# axiom_beta_shield_genio_v0_3_r1_2_ac7f6a.net
KiCad netlist of a schematic drawn in EAGLE
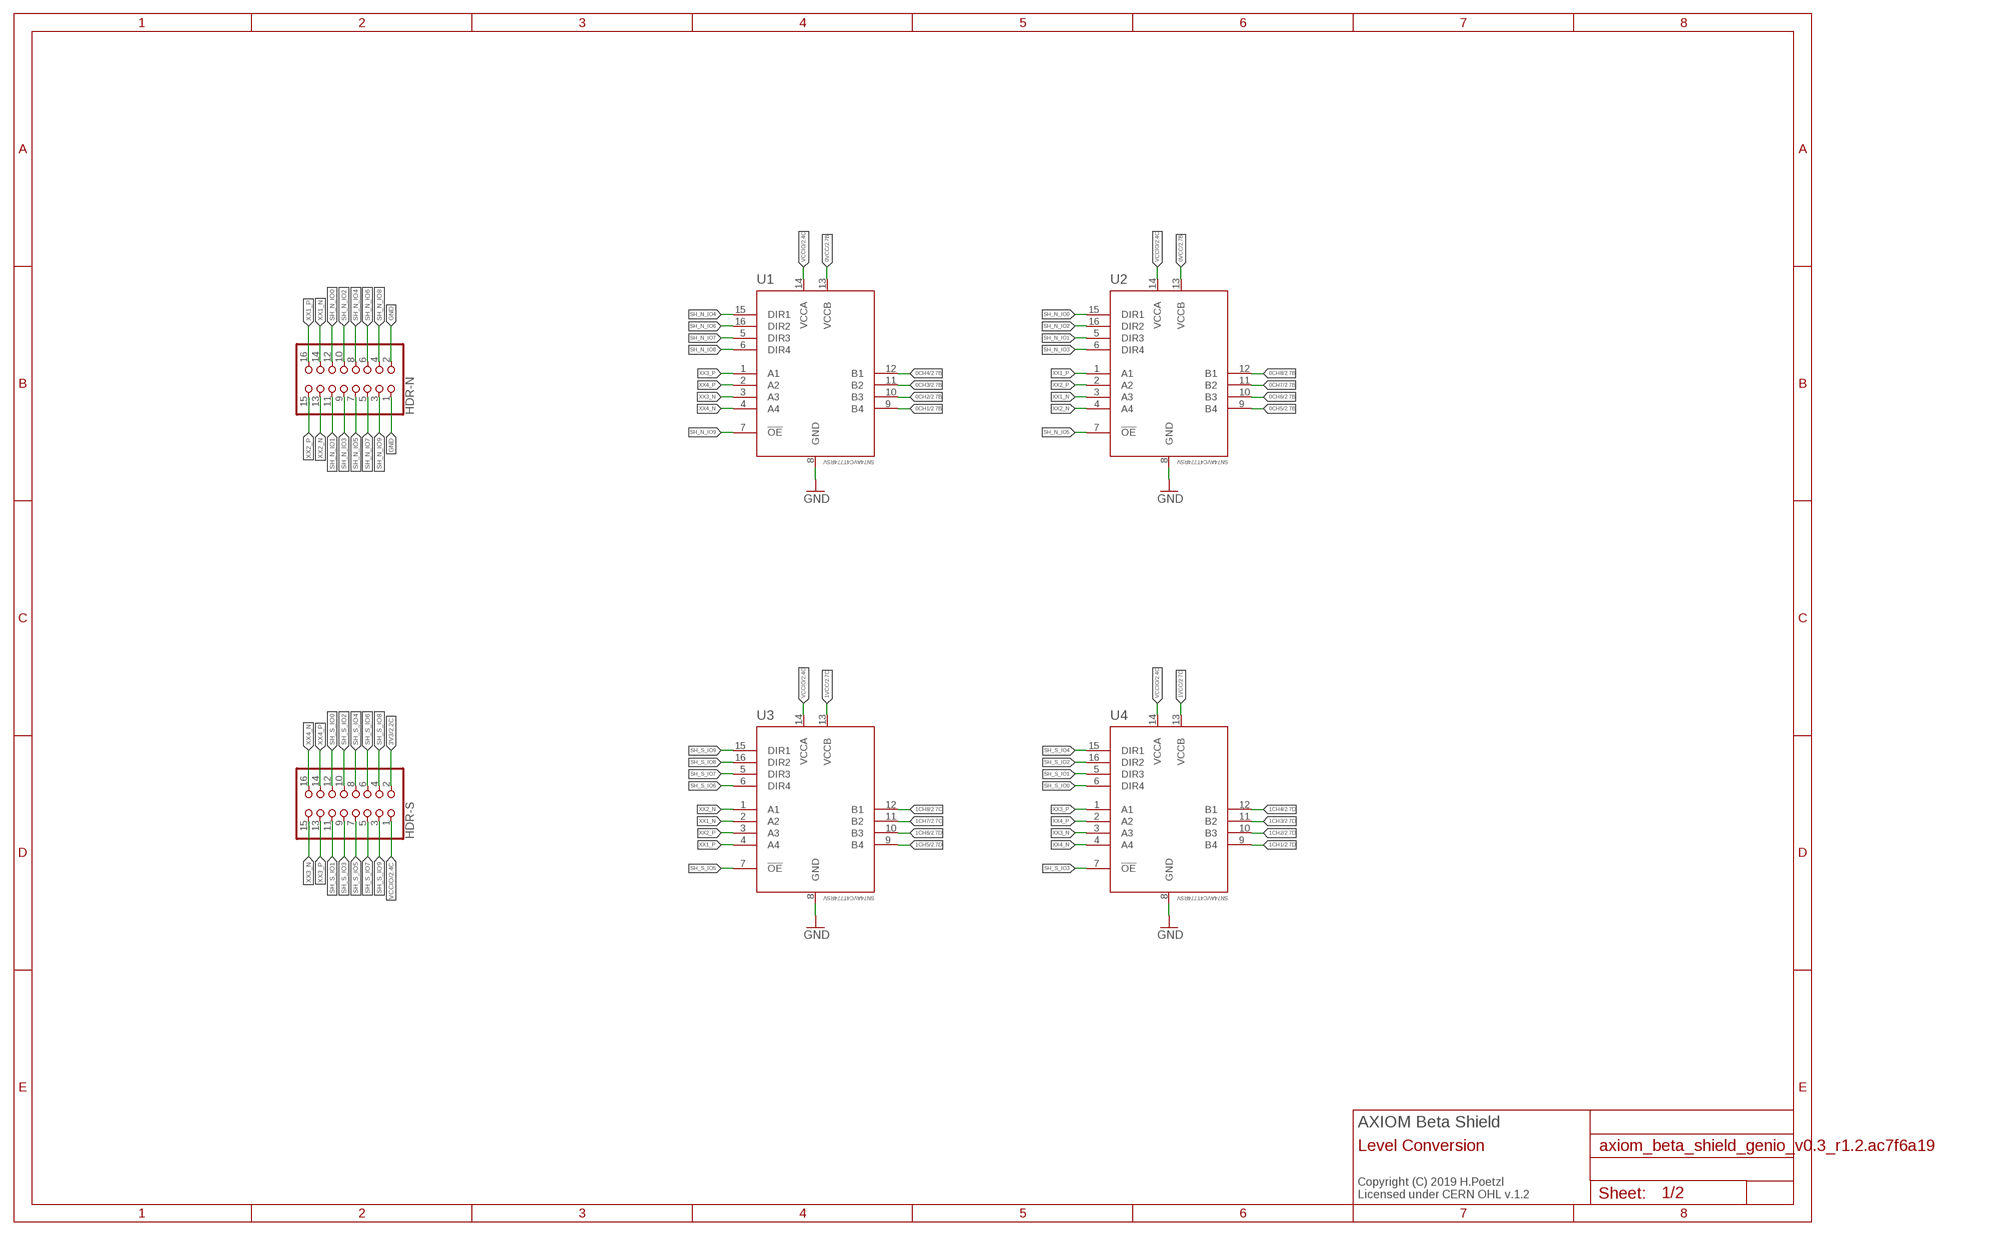
[diagram p0: schematic, sheet 1]
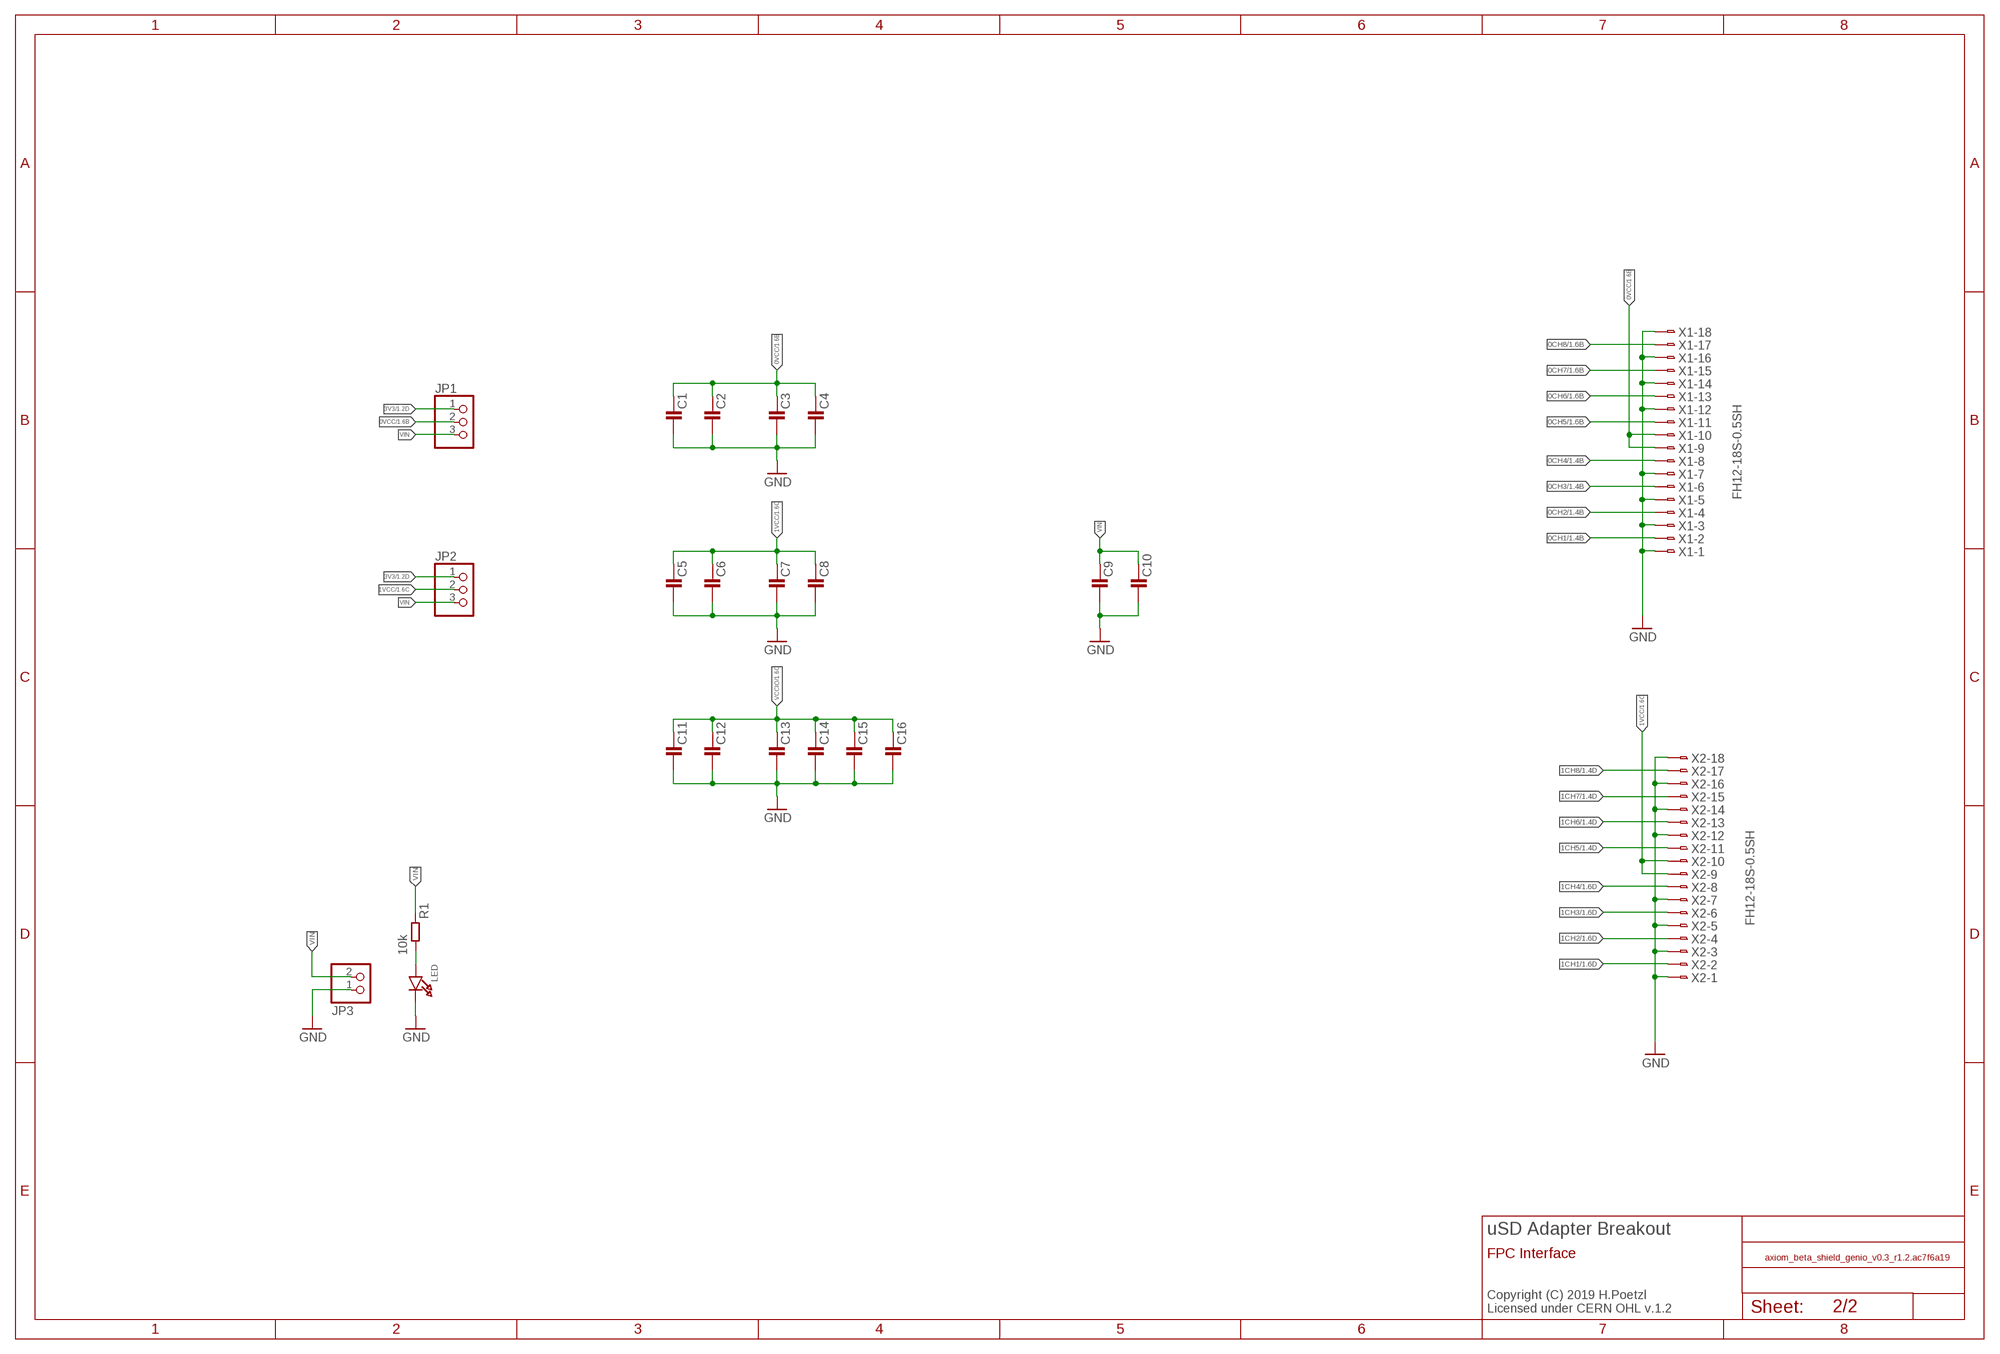
[diagram p1: schematic, sheet 2]

(export (version "E")
  (design (tool "Eeschema 10.0.6"))
  (components
    (comp (ref "HDR-N")
      (value "PINHD-2X08_2.00_SMD")
      (footprint "eagle-import:2X08M_SMD")
      (libsource (lib "eagle-import") (part "PINHD-2X08_2.00_SMD"))
    )
    (comp (ref "HDR-S")
      (value "PINHD-2X08_2.00_SMD")
      (footprint "eagle-import:2X08M_SMD")
      (libsource (lib "eagle-import") (part "PINHD-2X08_2.00_SMD"))
    )
    (comp (ref "U1")
      (value "SN74AVC4T774RSV")
      (footprint "eagle-import:QFN40P185X265X55-16N")
      (libsource (lib "eagle-import") (part "SN74AVC4T774RSV"))
    )
    (comp (ref "U2")
      (value "SN74AVC4T774RSV")
      (footprint "eagle-import:QFN40P185X265X55-16N")
      (libsource (lib "eagle-import") (part "SN74AVC4T774RSV"))
    )
    (comp (ref "U3")
      (value "SN74AVC4T774RSV")
      (footprint "eagle-import:QFN40P185X265X55-16N")
      (libsource (lib "eagle-import") (part "SN74AVC4T774RSV"))
    )
    (comp (ref "U4")
      (value "SN74AVC4T774RSV")
      (footprint "eagle-import:QFN40P185X265X55-16N")
      (libsource (lib "eagle-import") (part "SN74AVC4T774RSV"))
    )
    (comp (ref "C1")
      (value "C0603-C")
      (footprint "eagle-import:0603-C")
      (libsource (lib "eagle-import") (part "C0603-C"))
    )
    (comp (ref "C2")
      (value "C0603-C")
      (footprint "eagle-import:0603-C")
      (libsource (lib "eagle-import") (part "C0603-C"))
    )
    (comp (ref "C3")
      (value "C0402-C")
      (footprint "eagle-import:0402-C")
      (libsource (lib "eagle-import") (part "C0402-C"))
    )
    (comp (ref "C4")
      (value "C0402-C")
      (footprint "eagle-import:0402-C")
      (libsource (lib "eagle-import") (part "C0402-C"))
    )
    (comp (ref "C5")
      (value "C0603-C")
      (footprint "eagle-import:0603-C")
      (libsource (lib "eagle-import") (part "C0603-C"))
    )
    (comp (ref "C6")
      (value "C0603-C")
      (footprint "eagle-import:0603-C")
      (libsource (lib "eagle-import") (part "C0603-C"))
    )
    (comp (ref "C7")
      (value "C0402-C")
      (footprint "eagle-import:0402-C")
      (libsource (lib "eagle-import") (part "C0402-C"))
    )
    (comp (ref "C8")
      (value "C0402-C")
      (footprint "eagle-import:0402-C")
      (libsource (lib "eagle-import") (part "C0402-C"))
    )
    (comp (ref "C9")
      (value "C0603-C")
      (footprint "eagle-import:0603-C")
      (libsource (lib "eagle-import") (part "C0603-C"))
    )
    (comp (ref "C10")
      (value "C0603-C")
      (footprint "eagle-import:0603-C")
      (libsource (lib "eagle-import") (part "C0603-C"))
    )
    (comp (ref "C11")
      (value "C0603-C")
      (footprint "eagle-import:0603-C")
      (libsource (lib "eagle-import") (part "C0603-C"))
    )
    (comp (ref "C12")
      (value "C0603-C")
      (footprint "eagle-import:0603-C")
      (libsource (lib "eagle-import") (part "C0603-C"))
    )
    (comp (ref "C13")
      (value "C0402-C")
      (footprint "eagle-import:0402-C")
      (libsource (lib "eagle-import") (part "C0402-C"))
    )
    (comp (ref "C14")
      (value "C0402-C")
      (footprint "eagle-import:0402-C")
      (libsource (lib "eagle-import") (part "C0402-C"))
    )
    (comp (ref "C15")
      (value "C0402-C")
      (footprint "eagle-import:0402-C")
      (libsource (lib "eagle-import") (part "C0402-C"))
    )
    (comp (ref "C16")
      (value "C0402-C")
      (footprint "eagle-import:0402-C")
      (libsource (lib "eagle-import") (part "C0402-C"))
    )
    (comp (ref "JP1")
      (value "PINHD-1X03_2.00-90°-S")
      (footprint "eagle-import:1X03M_90-S")
      (libsource (lib "eagle-import") (part "PINHD-1X03_2.00-90°-S"))
    )
    (comp (ref "JP2")
      (value "PINHD-1X03_2.00-90°-S")
      (footprint "eagle-import:1X03M_90-S")
      (libsource (lib "eagle-import") (part "PINHD-1X03_2.00-90°-S"))
    )
    (comp (ref "JP3")
      (value "PINHD-1X02_2.54-90°")
      (footprint "eagle-import:1X02_90")
      (libsource (lib "eagle-import") (part "PINHD-1X02_2.54-90°"))
    )
    (comp (ref "LED")
      (value "LED0603_NOOUTLINE")
      (footprint "eagle-import:CHIPLED_0603_NOOUTLINE")
      (libsource (lib "eagle-import") (part "LED0603_NOOUTLINE"))
    )
    (comp (ref "R1")
      (value "10k")
      (footprint "eagle-import:0402-B")
      (libsource (lib "eagle-import") (part "R0402-B"))
    )
    (comp (ref "X1")
      (value "FH12-18S-0.5SH")
      (footprint "eagle-import:FH12-18S-0.5SH")
      (fields (field (name "MPN") "FH12-18S-0.5SH(55)"))
      (libsource (lib "eagle-import") (part "FH12-18S-0.5SH"))
    )
    (comp (ref "X2")
      (value "FH12-18S-0.5SH")
      (footprint "eagle-import:FH12-18S-0.5SH")
      (fields (field (name "MPN") "FH12-18S-0.5SH(55)"))
      (libsource (lib "eagle-import") (part "FH12-18S-0.5SH"))
    )
  )
  (nets
    (net (code "1") (name "0CH1") (class "Default")
      (node (ref "U1") (pin "9") (pinfunction "B4_9") (pintype "bidirectional"))
      (node (ref "X1") (pin "2") (pinfunction "1_2") (pintype "passive"))
    )
    (net (code "2") (name "0CH2") (class "Default")
      (node (ref "U1") (pin "10") (pinfunction "B3_10") (pintype "bidirectional"))
      (node (ref "X1") (pin "4") (pinfunction "1_4") (pintype "passive"))
    )
    (net (code "3") (name "0CH3") (class "Default")
      (node (ref "U1") (pin "11") (pinfunction "B2_11") (pintype "bidirectional"))
      (node (ref "X1") (pin "6") (pinfunction "1_6") (pintype "passive"))
    )
    (net (code "4") (name "0CH4") (class "Default")
      (node (ref "U1") (pin "12") (pinfunction "B1_12") (pintype "bidirectional"))
      (node (ref "X1") (pin "8") (pinfunction "1_8") (pintype "passive"))
    )
    (net (code "5") (name "0CH5") (class "Default")
      (node (ref "U2") (pin "9") (pinfunction "B4_9") (pintype "bidirectional"))
      (node (ref "X1") (pin "11") (pinfunction "1_11") (pintype "passive"))
    )
    (net (code "6") (name "0CH6") (class "Default")
      (node (ref "U2") (pin "10") (pinfunction "B3_10") (pintype "bidirectional"))
      (node (ref "X1") (pin "13") (pinfunction "1_13") (pintype "passive"))
    )
    (net (code "7") (name "0CH7") (class "Default")
      (node (ref "U2") (pin "11") (pinfunction "B2_11") (pintype "bidirectional"))
      (node (ref "X1") (pin "15") (pinfunction "1_15") (pintype "passive"))
    )
    (net (code "8") (name "0CH8") (class "Default")
      (node (ref "U2") (pin "12") (pinfunction "B1_12") (pintype "bidirectional"))
      (node (ref "X1") (pin "17") (pinfunction "1_17") (pintype "passive"))
    )
    (net (code "9") (name "0VCC") (class "Default")
      (node (ref "C1") (pin "1") (pinfunction "1_1") (pintype "passive"))
      (node (ref "C2") (pin "1") (pinfunction "1_1") (pintype "passive"))
      (node (ref "C3") (pin "1") (pinfunction "1_1") (pintype "passive"))
      (node (ref "C4") (pin "1") (pinfunction "1_1") (pintype "passive"))
      (node (ref "JP1") (pin "2") (pinfunction "2_2") (pintype "passive"))
      (node (ref "U1") (pin "13") (pinfunction "VCCB_13") (pintype "power_in"))
      (node (ref "U2") (pin "13") (pinfunction "VCCB_13") (pintype "power_in"))
      (node (ref "X1") (pin "10") (pinfunction "1_10") (pintype "passive"))
      (node (ref "X1") (pin "9") (pinfunction "1_9") (pintype "passive"))
    )
    (net (code "10") (name "1CH1") (class "Default")
      (node (ref "U4") (pin "9") (pinfunction "B4_9") (pintype "bidirectional"))
      (node (ref "X2") (pin "2") (pinfunction "1_2") (pintype "passive"))
    )
    (net (code "11") (name "1CH2") (class "Default")
      (node (ref "U4") (pin "10") (pinfunction "B3_10") (pintype "bidirectional"))
      (node (ref "X2") (pin "4") (pinfunction "1_4") (pintype "passive"))
    )
    (net (code "12") (name "1CH3") (class "Default")
      (node (ref "U4") (pin "11") (pinfunction "B2_11") (pintype "bidirectional"))
      (node (ref "X2") (pin "6") (pinfunction "1_6") (pintype "passive"))
    )
    (net (code "13") (name "1CH4") (class "Default")
      (node (ref "U4") (pin "12") (pinfunction "B1_12") (pintype "bidirectional"))
      (node (ref "X2") (pin "8") (pinfunction "1_8") (pintype "passive"))
    )
    (net (code "14") (name "1CH5") (class "Default")
      (node (ref "U3") (pin "9") (pinfunction "B4_9") (pintype "bidirectional"))
      (node (ref "X2") (pin "11") (pinfunction "1_11") (pintype "passive"))
    )
    (net (code "15") (name "1CH6") (class "Default")
      (node (ref "U3") (pin "10") (pinfunction "B3_10") (pintype "bidirectional"))
      (node (ref "X2") (pin "13") (pinfunction "1_13") (pintype "passive"))
    )
    (net (code "16") (name "1CH7") (class "Default")
      (node (ref "U3") (pin "11") (pinfunction "B2_11") (pintype "bidirectional"))
      (node (ref "X2") (pin "15") (pinfunction "1_15") (pintype "passive"))
    )
    (net (code "17") (name "1CH8") (class "Default")
      (node (ref "U3") (pin "12") (pinfunction "B1_12") (pintype "bidirectional"))
      (node (ref "X2") (pin "17") (pinfunction "1_17") (pintype "passive"))
    )
    (net (code "18") (name "1VCC") (class "Default")
      (node (ref "C5") (pin "1") (pinfunction "1_1") (pintype "passive"))
      (node (ref "C6") (pin "1") (pinfunction "1_1") (pintype "passive"))
      (node (ref "C7") (pin "1") (pinfunction "1_1") (pintype "passive"))
      (node (ref "C8") (pin "1") (pinfunction "1_1") (pintype "passive"))
      (node (ref "JP2") (pin "2") (pinfunction "2_2") (pintype "passive"))
      (node (ref "U3") (pin "13") (pinfunction "VCCB_13") (pintype "power_in"))
      (node (ref "U4") (pin "13") (pinfunction "VCCB_13") (pintype "power_in"))
      (node (ref "X2") (pin "10") (pinfunction "1_10") (pintype "passive"))
      (node (ref "X2") (pin "9") (pinfunction "1_9") (pintype "passive"))
    )
    (net (code "19") (name "3V3") (class "Default")
      (node (ref "HDR-S") (pin "2") (pinfunction "2_2") (pintype "passive"))
      (node (ref "JP1") (pin "1") (pinfunction "1_1") (pintype "passive"))
      (node (ref "JP2") (pin "1") (pinfunction "1_1") (pintype "passive"))
    )
    (net (code "20") (name "GND") (class "Default")
      (node (ref "C1") (pin "2") (pinfunction "2_2") (pintype "passive"))
      (node (ref "C10") (pin "2") (pinfunction "2_2") (pintype "passive"))
      (node (ref "C11") (pin "2") (pinfunction "2_2") (pintype "passive"))
      (node (ref "C12") (pin "2") (pinfunction "2_2") (pintype "passive"))
      (node (ref "C13") (pin "2") (pinfunction "2_2") (pintype "passive"))
      (node (ref "C14") (pin "2") (pinfunction "2_2") (pintype "passive"))
      (node (ref "C15") (pin "2") (pinfunction "2_2") (pintype "passive"))
      (node (ref "C16") (pin "2") (pinfunction "2_2") (pintype "passive"))
      (node (ref "C2") (pin "2") (pinfunction "2_2") (pintype "passive"))
      (node (ref "C3") (pin "2") (pinfunction "2_2") (pintype "passive"))
      (node (ref "C4") (pin "2") (pinfunction "2_2") (pintype "passive"))
      (node (ref "C5") (pin "2") (pinfunction "2_2") (pintype "passive"))
      (node (ref "C6") (pin "2") (pinfunction "2_2") (pintype "passive"))
      (node (ref "C7") (pin "2") (pinfunction "2_2") (pintype "passive"))
      (node (ref "C8") (pin "2") (pinfunction "2_2") (pintype "passive"))
      (node (ref "C9") (pin "2") (pinfunction "2_2") (pintype "passive"))
      (node (ref "HDR-N") (pin "1") (pinfunction "1_1") (pintype "passive"))
      (node (ref "HDR-N") (pin "2") (pinfunction "2_2") (pintype "passive"))
      (node (ref "JP3") (pin "1") (pinfunction "1_1") (pintype "passive"))
      (node (ref "LED") (pin "C") (pinfunction "C_C") (pintype "passive"))
      (node (ref "U1") (pin "8") (pinfunction "GND_8") (pintype "passive"))
      (node (ref "U2") (pin "8") (pinfunction "GND_8") (pintype "passive"))
      (node (ref "U3") (pin "8") (pinfunction "GND_8") (pintype "passive"))
      (node (ref "U4") (pin "8") (pinfunction "GND_8") (pintype "passive"))
      (node (ref "X1") (pin "1") (pinfunction "1_1") (pintype "passive"))
      (node (ref "X1") (pin "12") (pinfunction "1_12") (pintype "passive"))
      (node (ref "X1") (pin "14") (pinfunction "1_14") (pintype "passive"))
      (node (ref "X1") (pin "16") (pinfunction "1_16") (pintype "passive"))
      (node (ref "X1") (pin "18") (pinfunction "1_18") (pintype "passive"))
      (node (ref "X1") (pin "3") (pinfunction "1_3") (pintype "passive"))
      (node (ref "X1") (pin "5") (pinfunction "1_5") (pintype "passive"))
      (node (ref "X1") (pin "7") (pinfunction "1_7") (pintype "passive"))
      (node (ref "X2") (pin "1") (pinfunction "1_1") (pintype "passive"))
      (node (ref "X2") (pin "12") (pinfunction "1_12") (pintype "passive"))
      (node (ref "X2") (pin "14") (pinfunction "1_14") (pintype "passive"))
      (node (ref "X2") (pin "16") (pinfunction "1_16") (pintype "passive"))
      (node (ref "X2") (pin "18") (pinfunction "1_18") (pintype "passive"))
      (node (ref "X2") (pin "3") (pinfunction "1_3") (pintype "passive"))
      (node (ref "X2") (pin "5") (pinfunction "1_5") (pintype "passive"))
      (node (ref "X2") (pin "7") (pinfunction "1_7") (pintype "passive"))
    )
    (net (code "21") (name "Net-(LED-PadA)") (class "Default")
      (node (ref "LED") (pin "A") (pinfunction "A_A") (pintype "passive"))
      (node (ref "R1") (pin "2") (pinfunction "2_2") (pintype "passive"))
    )
    (net (code "22") (name "SH_N_IO0") (class "Default")
      (node (ref "HDR-N") (pin "12") (pinfunction "12_12") (pintype "passive"))
      (node (ref "U2") (pin "15") (pinfunction "DIR1_15") (pintype "input"))
    )
    (net (code "23") (name "SH_N_IO1") (class "Default")
      (node (ref "HDR-N") (pin "11") (pinfunction "11_11") (pintype "passive"))
      (node (ref "U2") (pin "5") (pinfunction "DIR3_5") (pintype "input"))
    )
    (net (code "24") (name "SH_N_IO2") (class "Default")
      (node (ref "HDR-N") (pin "10") (pinfunction "10_10") (pintype "passive"))
      (node (ref "U2") (pin "16") (pinfunction "DIR2_16") (pintype "input"))
    )
    (net (code "25") (name "SH_N_IO3") (class "Default")
      (node (ref "HDR-N") (pin "9") (pinfunction "9_9") (pintype "passive"))
      (node (ref "U2") (pin "6") (pinfunction "DIR4_6") (pintype "input"))
    )
    (net (code "26") (name "SH_N_IO4") (class "Default")
      (node (ref "HDR-N") (pin "8") (pinfunction "8_8") (pintype "passive"))
      (node (ref "U1") (pin "15") (pinfunction "DIR1_15") (pintype "input"))
    )
    (net (code "27") (name "SH_N_IO5") (class "Default")
      (node (ref "HDR-N") (pin "7") (pinfunction "7_7") (pintype "passive"))
      (node (ref "U2") (pin "7") (pinfunction "~{OE}_7") (pintype "input"))
    )
    (net (code "28") (name "SH_N_IO6") (class "Default")
      (node (ref "HDR-N") (pin "6") (pinfunction "6_6") (pintype "passive"))
      (node (ref "U1") (pin "16") (pinfunction "DIR2_16") (pintype "input"))
    )
    (net (code "29") (name "SH_N_IO7") (class "Default")
      (node (ref "HDR-N") (pin "5") (pinfunction "5_5") (pintype "passive"))
      (node (ref "U1") (pin "5") (pinfunction "DIR3_5") (pintype "input"))
    )
    (net (code "30") (name "SH_N_IO8") (class "Default")
      (node (ref "HDR-N") (pin "4") (pinfunction "4_4") (pintype "passive"))
      (node (ref "U1") (pin "6") (pinfunction "DIR4_6") (pintype "input"))
    )
    (net (code "31") (name "SH_N_IO9") (class "Default")
      (node (ref "HDR-N") (pin "3") (pinfunction "3_3") (pintype "passive"))
      (node (ref "U1") (pin "7") (pinfunction "~{OE}_7") (pintype "input"))
    )
    (net (code "32") (name "SH_S_IO0") (class "Default")
      (node (ref "HDR-S") (pin "12") (pinfunction "12_12") (pintype "passive"))
      (node (ref "U4") (pin "6") (pinfunction "DIR4_6") (pintype "input"))
    )
    (net (code "33") (name "SH_S_IO1") (class "Default")
      (node (ref "HDR-S") (pin "11") (pinfunction "11_11") (pintype "passive"))
      (node (ref "U4") (pin "5") (pinfunction "DIR3_5") (pintype "input"))
    )
    (net (code "34") (name "SH_S_IO2") (class "Default")
      (node (ref "HDR-S") (pin "10") (pinfunction "10_10") (pintype "passive"))
      (node (ref "U4") (pin "16") (pinfunction "DIR2_16") (pintype "input"))
    )
    (net (code "35") (name "SH_S_IO3") (class "Default")
      (node (ref "HDR-S") (pin "9") (pinfunction "9_9") (pintype "passive"))
      (node (ref "U4") (pin "7") (pinfunction "~{OE}_7") (pintype "input"))
    )
    (net (code "36") (name "SH_S_IO4") (class "Default")
      (node (ref "HDR-S") (pin "8") (pinfunction "8_8") (pintype "passive"))
      (node (ref "U4") (pin "15") (pinfunction "DIR1_15") (pintype "input"))
    )
    (net (code "37") (name "SH_S_IO5") (class "Default")
      (node (ref "HDR-S") (pin "7") (pinfunction "7_7") (pintype "passive"))
      (node (ref "U3") (pin "7") (pinfunction "~{OE}_7") (pintype "input"))
    )
    (net (code "38") (name "SH_S_IO6") (class "Default")
      (node (ref "HDR-S") (pin "6") (pinfunction "6_6") (pintype "passive"))
      (node (ref "U3") (pin "6") (pinfunction "DIR4_6") (pintype "input"))
    )
    (net (code "39") (name "SH_S_IO7") (class "Default")
      (node (ref "HDR-S") (pin "5") (pinfunction "5_5") (pintype "passive"))
      (node (ref "U3") (pin "5") (pinfunction "DIR3_5") (pintype "input"))
    )
    (net (code "40") (name "SH_S_IO8") (class "Default")
      (node (ref "HDR-S") (pin "4") (pinfunction "4_4") (pintype "passive"))
      (node (ref "U3") (pin "16") (pinfunction "DIR2_16") (pintype "input"))
    )
    (net (code "41") (name "SH_S_IO9") (class "Default")
      (node (ref "HDR-S") (pin "3") (pinfunction "3_3") (pintype "passive"))
      (node (ref "U3") (pin "15") (pinfunction "DIR1_15") (pintype "input"))
    )
    (net (code "42") (name "VCCIO") (class "Default")
      (node (ref "C11") (pin "1") (pinfunction "1_1") (pintype "passive"))
      (node (ref "C12") (pin "1") (pinfunction "1_1") (pintype "passive"))
      (node (ref "C13") (pin "1") (pinfunction "1_1") (pintype "passive"))
      (node (ref "C14") (pin "1") (pinfunction "1_1") (pintype "passive"))
      (node (ref "C15") (pin "1") (pinfunction "1_1") (pintype "passive"))
      (node (ref "C16") (pin "1") (pinfunction "1_1") (pintype "passive"))
      (node (ref "HDR-S") (pin "1") (pinfunction "1_1") (pintype "passive"))
      (node (ref "U1") (pin "14") (pinfunction "VCCA_14") (pintype "power_in"))
      (node (ref "U2") (pin "14") (pinfunction "VCCA_14") (pintype "power_in"))
      (node (ref "U3") (pin "14") (pinfunction "VCCA_14") (pintype "power_in"))
      (node (ref "U4") (pin "14") (pinfunction "VCCA_14") (pintype "power_in"))
    )
    (net (code "43") (name "VIN") (class "Default")
      (node (ref "C10") (pin "1") (pinfunction "1_1") (pintype "passive"))
      (node (ref "C9") (pin "1") (pinfunction "1_1") (pintype "passive"))
      (node (ref "JP1") (pin "3") (pinfunction "3_3") (pintype "passive"))
      (node (ref "JP2") (pin "3") (pinfunction "3_3") (pintype "passive"))
      (node (ref "JP3") (pin "2") (pinfunction "2_2") (pintype "passive"))
      (node (ref "R1") (pin "1") (pinfunction "1_1") (pintype "passive"))
    )
    (net (code "44") (name "XX1_N") (class "Default")
      (node (ref "HDR-N") (pin "14") (pinfunction "14_14") (pintype "passive"))
      (node (ref "U2") (pin "3") (pinfunction "A3_3") (pintype "bidirectional"))
      (node (ref "U3") (pin "2") (pinfunction "A2_2") (pintype "bidirectional"))
    )
    (net (code "45") (name "XX1_P") (class "Default")
      (node (ref "HDR-N") (pin "16") (pinfunction "16_16") (pintype "passive"))
      (node (ref "U2") (pin "1") (pinfunction "A1_1") (pintype "bidirectional"))
      (node (ref "U3") (pin "4") (pinfunction "A4_4") (pintype "bidirectional"))
    )
    (net (code "46") (name "XX2_N") (class "Default")
      (node (ref "HDR-N") (pin "13") (pinfunction "13_13") (pintype "passive"))
      (node (ref "U2") (pin "4") (pinfunction "A4_4") (pintype "bidirectional"))
      (node (ref "U3") (pin "1") (pinfunction "A1_1") (pintype "bidirectional"))
    )
    (net (code "47") (name "XX2_P") (class "Default")
      (node (ref "HDR-N") (pin "15") (pinfunction "15_15") (pintype "passive"))
      (node (ref "U2") (pin "2") (pinfunction "A2_2") (pintype "bidirectional"))
      (node (ref "U3") (pin "3") (pinfunction "A3_3") (pintype "bidirectional"))
    )
    (net (code "48") (name "XX3_N") (class "Default")
      (node (ref "HDR-S") (pin "15") (pinfunction "15_15") (pintype "passive"))
      (node (ref "U1") (pin "3") (pinfunction "A3_3") (pintype "bidirectional"))
      (node (ref "U4") (pin "3") (pinfunction "A3_3") (pintype "bidirectional"))
    )
    (net (code "49") (name "XX3_P") (class "Default")
      (node (ref "HDR-S") (pin "13") (pinfunction "13_13") (pintype "passive"))
      (node (ref "U1") (pin "1") (pinfunction "A1_1") (pintype "bidirectional"))
      (node (ref "U4") (pin "1") (pinfunction "A1_1") (pintype "bidirectional"))
    )
    (net (code "50") (name "XX4_N") (class "Default")
      (node (ref "HDR-S") (pin "16") (pinfunction "16_16") (pintype "passive"))
      (node (ref "U1") (pin "4") (pinfunction "A4_4") (pintype "bidirectional"))
      (node (ref "U4") (pin "4") (pinfunction "A4_4") (pintype "bidirectional"))
    )
    (net (code "51") (name "XX4_P") (class "Default")
      (node (ref "HDR-S") (pin "14") (pinfunction "14_14") (pintype "passive"))
      (node (ref "U1") (pin "2") (pinfunction "A2_2") (pintype "bidirectional"))
      (node (ref "U4") (pin "2") (pinfunction "A2_2") (pintype "bidirectional"))
    )
  )
)
